# MCU063B_USB.net
KiCad netlist of a schematic drawn in Altium Designer
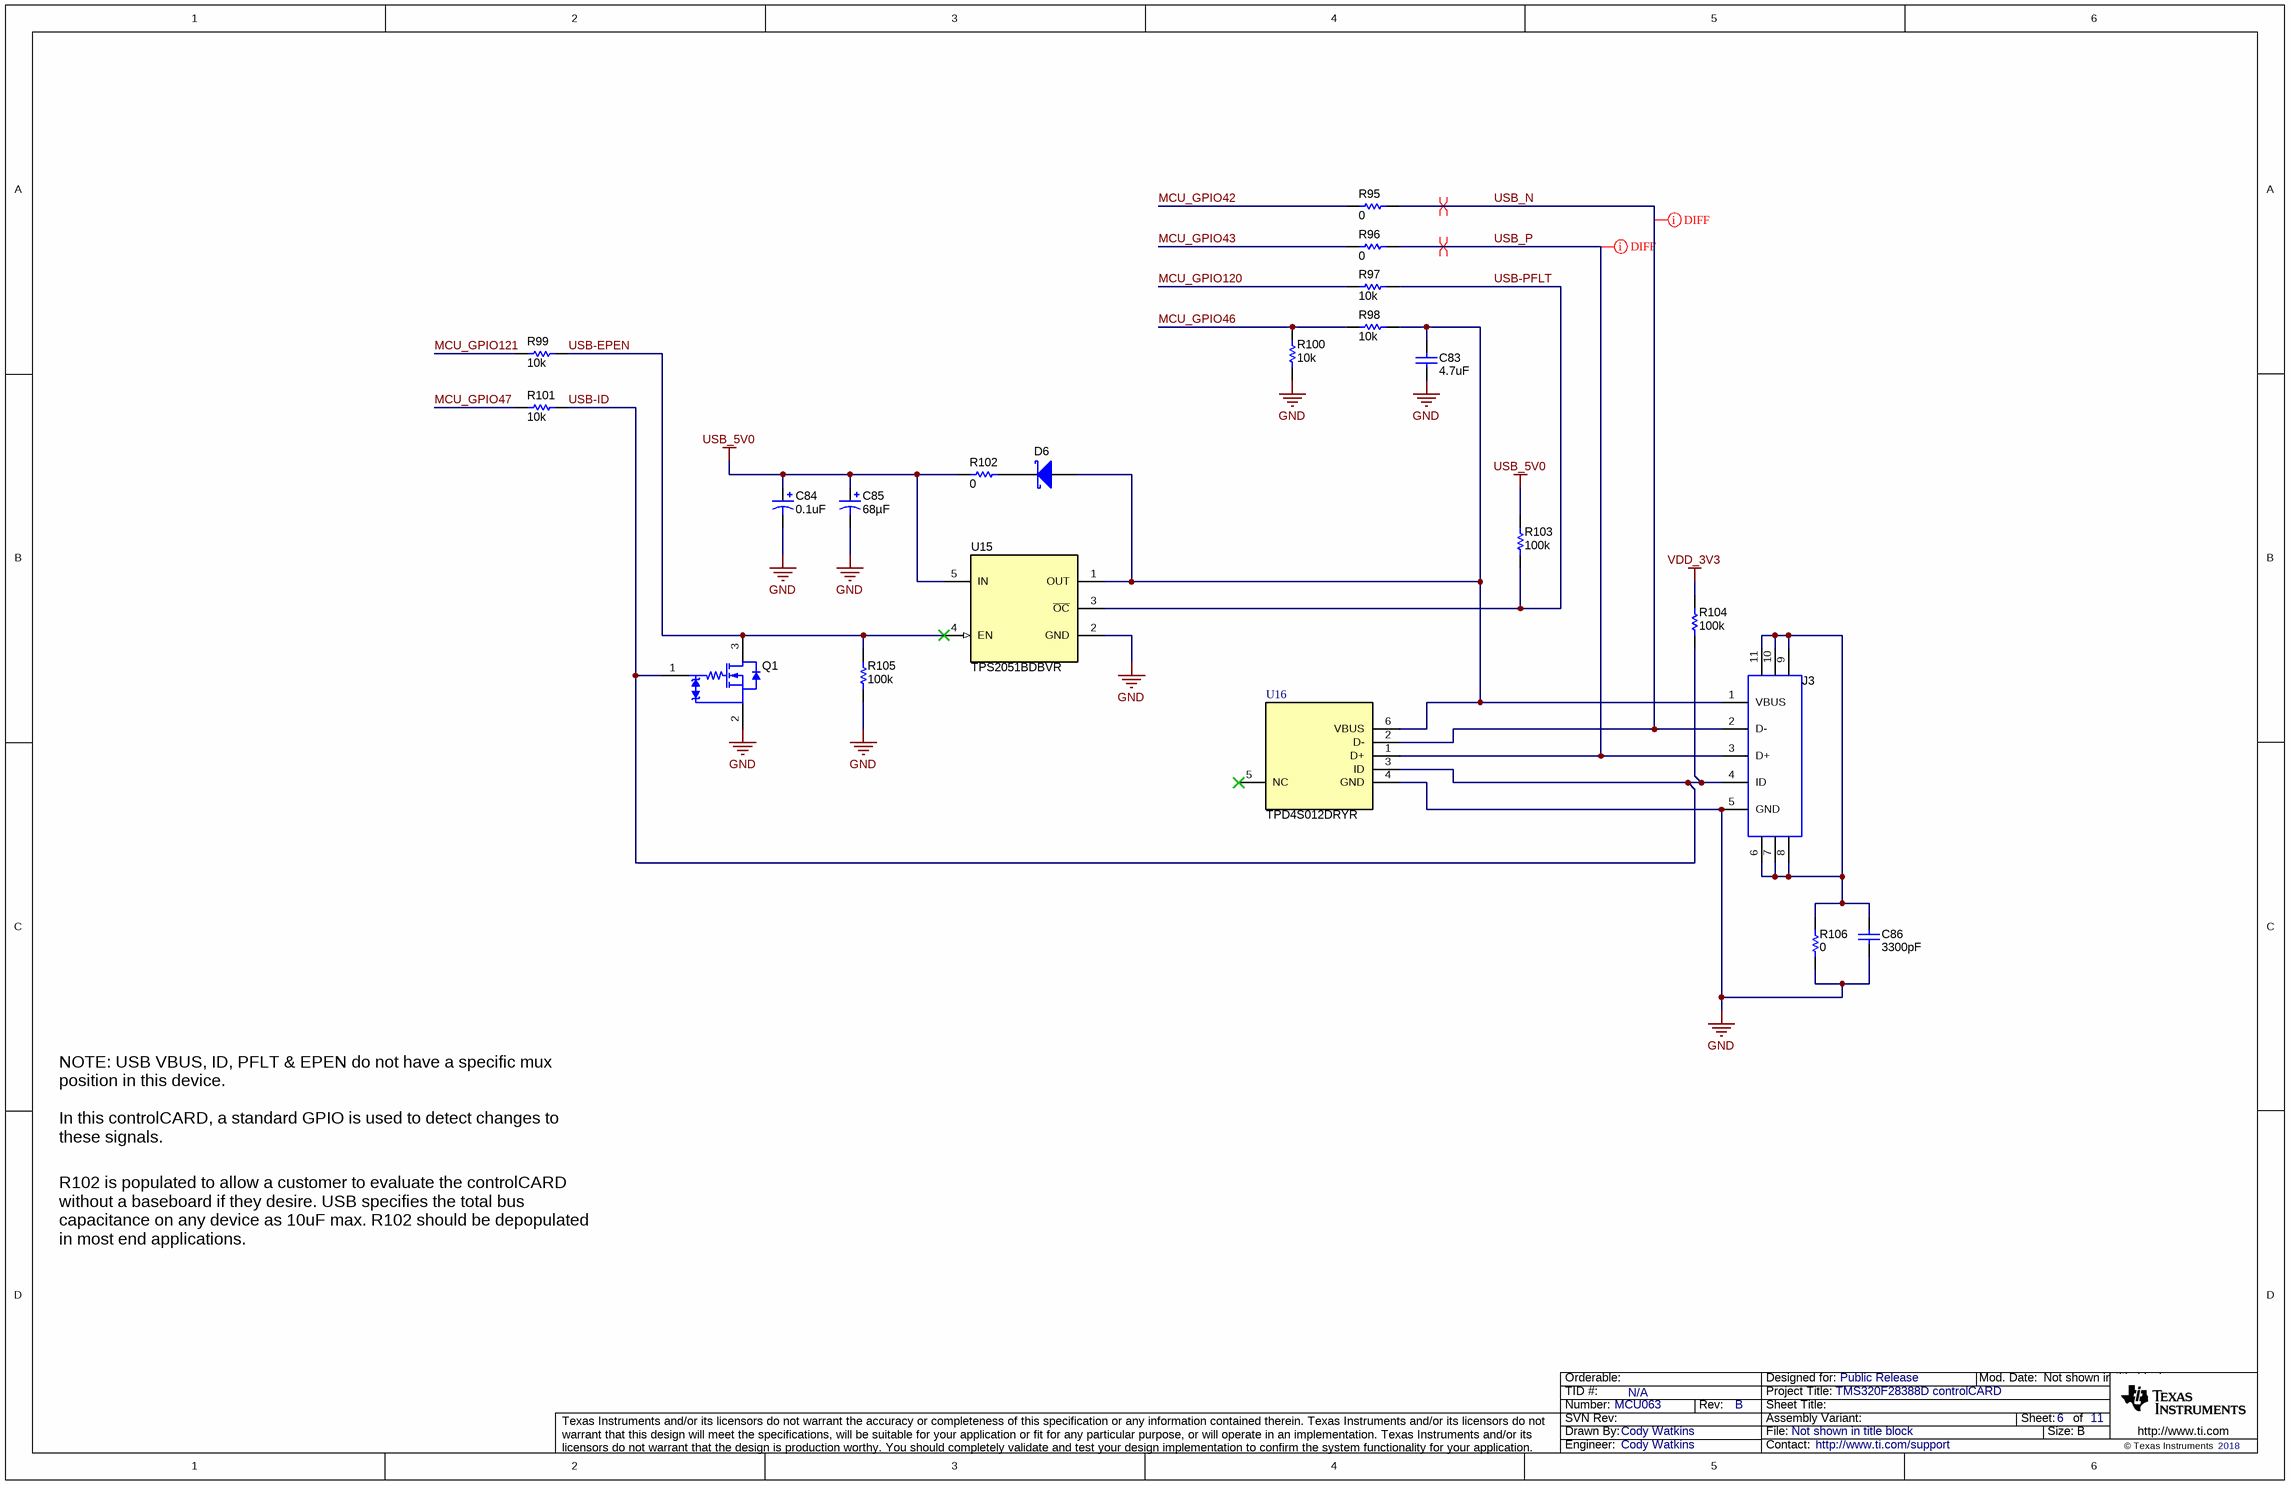
[diagram p0: MCU063B_USB.SchDoc]

(export (version "E")
  (design (tool "Eeschema 10.0.6"))
  (components
    (comp (ref "C83")
      (value "C0603C475K9PACTU")
      (footprint "0603")
      (description "CAP, CERM, 4.7 uF, 6.3 V, +/- 10%, X5R, 0603")
      (fields
        (field (name "MANUFACTURER") "Kemet")
        (field (name "VALUEDISPLAYED") "4.7uF")
        (field (name "PUBLISHER") "Texas Instruments")
      )
      (libsource (lib "Altium Vault - TI") (part "Capacitor"))
    )
    (comp (ref "C84")
      (value "293D104X9035A2TE3")
      (footprint "3216-18")
      (description "CAP, TA, 0.1 uF, 35 V, +/- 10%, 20 ohm, SMD")
      (fields
        (field (name "MANUFACTURER") "Vishay-Sprague")
        (field (name "VALUEDISPLAYED") "0.1uF")
        (field (name "PUBLISHER") "Texas Instruments")
      )
      (libsource (lib "Altium Vault - TI") (part "Cap_Polarized"))
    )
    (comp (ref "C85")
      (value "TLJA686M010R1500")
      (footprint "3216-18")
      (description "CAP, TA, 68 µF, 10 V, +/- 20%, 1.5 ohm, SMD")
      (fields (field (name "MANUFACTURER") "AVX") (field (name "VALUEDISPLAYED") "68µF"))
      (libsource (lib "Altium Vault - TI") (part "Cap_Polarized"))
    )
    (comp (ref "C86")
      (value "CGA2B2X7R1H332K050BA")
      (footprint "0402")
      (description "CAP, CERM, 3300 pF, 50 V, +/- 10%, X7R, AEC-Q200 Grade 1, 0402")
      (fields
        (field (name "MANUFACTURER") "TDK")
        (field (name "VALUEDISPLAYED") "3300pF")
        (field (name "PUBLISHER") "Texas Instruments")
      )
      (libsource (lib "Altium Vault - TI") (part "Capacitor"))
    )
    (comp (ref "D6")
      (value "MBRM110ET1G")
      (footprint "POWERMITE")
      (description "Diode, Schottky, 10 V, 1 A, AEC-Q101, POWERMITE")
      (fields (field (name "MANUFACTURER") "ON Semiconductor"))
      (libsource (lib "Altium Vault - TI") (part "DIODE_SCHOTTKY"))
    )
    (comp (ref "J3")
      (value "1051640001")
      (footprint "Molex_1051640001")
      (description "Receptacle, USB 2.0, Micro B, 5 Position, R/A, SMT")
      (fields (field (name "MANUFACTURER") "Molex") (field (name "PUBLISHER") "Texas Instruments"))
      (libsource (lib "Altium Vault - TI") (part "CONN_USB_MicroMini_6Shld"))
    )
    (comp (ref "Q1")
      (value "NTA7002NT1G")
      (footprint "SOT-416")
      (description "MOSFET, N-CH, 30 V, 0.154 A, AEC-Q101, SOT-416")
      (fields (field (name "MANUFACTURER") "ON Semiconductor"))
      (libsource (lib "Altium Vault - TI") (part "MOSFET_N_D3G1S2_PD5_RES"))
    )
    (comp (ref "R95")
      (value "CRCW04020000Z0ED")
      (footprint "0402")
      (description "RES, 0, 5%, 0.063 W, AEC-Q200 Grade 0, 0402")
      (fields (field (name "VALUEDISPLAYED") "0") (field (name "MANUFACTURER") "Vishay-Dale"))
      (libsource (lib "Altium Vault - TI") (part "Resistor"))
    )
    (comp (ref "R96")
      (value "CRCW04020000Z0ED")
      (footprint "0402")
      (description "RES, 0, 5%, 0.063 W, AEC-Q200 Grade 0, 0402")
      (fields (field (name "VALUEDISPLAYED") "0") (field (name "MANUFACTURER") "Vishay-Dale"))
      (libsource (lib "Altium Vault - TI") (part "Resistor"))
    )
    (comp (ref "R97")
      (value "ERJ-6GEYJ103V")
      (footprint "0805_HV")
      (description "RES, 10 k, 5%, 0.125 W, AEC-Q200 Grade 0, 0805")
      (fields (field (name "MANUFACTURER") "Panasonic") (field (name "VALUEDISPLAYED") "10k"))
      (libsource (lib "Altium Vault - TI") (part "Resistor"))
    )
    (comp (ref "R98")
      (value "ERJ-6GEYJ103V")
      (footprint "0805_HV")
      (description "RES, 10 k, 5%, 0.125 W, AEC-Q200 Grade 0, 0805")
      (fields (field (name "MANUFACTURER") "Panasonic") (field (name "VALUEDISPLAYED") "10k"))
      (libsource (lib "Altium Vault - TI") (part "Resistor"))
    )
    (comp (ref "R99")
      (value "ERJ-6GEYJ103V")
      (footprint "0805_HV")
      (description "RES, 10 k, 5%, 0.125 W, AEC-Q200 Grade 0, 0805")
      (fields (field (name "MANUFACTURER") "Panasonic") (field (name "VALUEDISPLAYED") "10k"))
      (libsource (lib "Altium Vault - TI") (part "Resistor"))
    )
    (comp (ref "R100")
      (value "ERJ-6GEYJ103V")
      (footprint "0805_HV")
      (description "RES, 10 k, 5%, 0.125 W, AEC-Q200 Grade 0, 0805")
      (fields (field (name "MANUFACTURER") "Panasonic") (field (name "VALUEDISPLAYED") "10k"))
      (libsource (lib "Altium Vault - TI") (part "Resistor"))
    )
    (comp (ref "R101")
      (value "ERJ-6GEYJ103V")
      (footprint "0805_HV")
      (description "RES, 10 k, 5%, 0.125 W, AEC-Q200 Grade 0, 0805")
      (fields (field (name "MANUFACTURER") "Panasonic") (field (name "VALUEDISPLAYED") "10k"))
      (libsource (lib "Altium Vault - TI") (part "Resistor"))
    )
    (comp (ref "R102")
      (value "CRCW04020000Z0ED")
      (footprint "0402")
      (description "RES, 0, 5%, 0.063 W, AEC-Q200 Grade 0, 0402")
      (fields (field (name "VALUEDISPLAYED") "0") (field (name "MANUFACTURER") "Vishay-Dale"))
      (libsource (lib "Altium Vault - TI") (part "Resistor"))
    )
    (comp (ref "R103")
      (value "ERJ-3GEYJ104V")
      (footprint "0603")
      (description "RES, 100 k, 5%, 0.1 W, AEC-Q200 Grade 0, 0603")
      (fields
        (field (name "MANUFACTURER") "Panasonic")
        (field (name "VALUEDISPLAYED") "100k")
        (field (name "PUBLISHER") "Texas Instruments")
      )
      (libsource (lib "Altium Vault - TI") (part "Resistor"))
    )
    (comp (ref "R104")
      (value "ERJ-3GEYJ104V")
      (footprint "0603")
      (description "RES, 100 k, 5%, 0.1 W, AEC-Q200 Grade 0, 0603")
      (fields
        (field (name "MANUFACTURER") "Panasonic")
        (field (name "VALUEDISPLAYED") "100k")
        (field (name "PUBLISHER") "Texas Instruments")
      )
      (libsource (lib "Altium Vault - TI") (part "Resistor"))
    )
    (comp (ref "R105")
      (value "ERJ-3GEYJ104V")
      (footprint "0603")
      (description "RES, 100 k, 5%, 0.1 W, AEC-Q200 Grade 0, 0603")
      (fields
        (field (name "MANUFACTURER") "Panasonic")
        (field (name "VALUEDISPLAYED") "100k")
        (field (name "PUBLISHER") "Texas Instruments")
      )
      (libsource (lib "Altium Vault - TI") (part "Resistor"))
    )
    (comp (ref "R106")
      (value "CRCW04020000Z0ED")
      (footprint "0402")
      (description "RES, 0, 5%, 0.063 W, AEC-Q200 Grade 0, 0402")
      (fields (field (name "VALUEDISPLAYED") "0") (field (name "MANUFACTURER") "Vishay-Dale"))
      (libsource (lib "Altium Vault - TI") (part "Resistor"))
    )
    (comp (ref "U15")
      (value "TPS2051BDBVR")
      (footprint "DBV0005A_N")
      (description "Single, Current-Limited, Power-Distribution Switch, DBV0005A (SOT-23-5)")
      (fields
        (field (name "ALTERNATE PARTNUMBER") "TPS2051BDBVT")
        (field (name "MANUFACTURER") "Texas Instruments")
        (field (name "PARTNUMBER") "TPS2051BDBVR")
        (field (name "PUBLISHER") "Texas Instruments")
      )
      (libsource (lib "Altium Vault - TI") (part "TPS2051DBV"))
    )
    (comp (ref "U16")
      (value "TPD4S012DRYR")
      (footprint "DRY0006A")
      (description "4-Channel USB ESD Solution with Power Clamp, DRY0006A (USON-6)")
      (fields (field (name "MANUFACTURER") "Texas Instruments") (field (name "PARTNUMBER") "TPD4S012DRYR"))
      (libsource (lib "Altium Vault - TI") (part "TI-TPD4S012-SON_DRY-6"))
    )
  )
  (nets
    (net (code "1") (name "/MCU_GPIO42") (class "Default")
      (node (ref "R95") (pin "1") (pinfunction "1_1") (pintype "passive"))
    )
    (net (code "2") (name "/MCU_GPIO43") (class "Default")
      (node (ref "R96") (pin "1") (pinfunction "1_1") (pintype "passive"))
    )
    (net (code "3") (name "/MCU_GPIO46") (class "Default")
      (node (ref "R100") (pin "2") (pinfunction "2_2") (pintype "passive"))
      (node (ref "R98") (pin "1") (pinfunction "1_1") (pintype "passive"))
    )
    (net (code "4") (name "/MCU_GPIO47") (class "Default")
      (node (ref "R101") (pin "1") (pinfunction "1_1") (pintype "passive"))
    )
    (net (code "5") (name "/MCU_GPIO120") (class "Default")
      (node (ref "R97") (pin "1") (pinfunction "1_1") (pintype "passive"))
    )
    (net (code "6") (name "/MCU_GPIO121") (class "Default")
      (node (ref "R99") (pin "1") (pinfunction "1_1") (pintype "passive"))
    )
    (net (code "7") (name "/USB-EPEN") (class "Default")
      (node (ref "Q1") (pin "3") (pinfunction "D_3") (pintype "passive"))
      (node (ref "R105") (pin "1") (pinfunction "1_1") (pintype "passive"))
      (node (ref "R99") (pin "2") (pinfunction "2_2") (pintype "passive"))
      (node (ref "U15") (pin "4") (pinfunction "EN_4") (pintype "input"))
    )
    (net (code "8") (name "/USB-ID") (class "Default")
      (node (ref "J3") (pin "4") (pinfunction "ID_4") (pintype "passive"))
      (node (ref "Q1") (pin "1") (pinfunction "G_1") (pintype "passive"))
      (node (ref "R101") (pin "2") (pinfunction "2_2") (pintype "passive"))
      (node (ref "R104") (pin "2") (pinfunction "2_2") (pintype "passive"))
      (node (ref "U16") (pin "3") (pinfunction "ID_3") (pintype "passive"))
    )
    (net (code "9") (name "/USB-PFLT") (class "Default")
      (node (ref "R103") (pin "2") (pinfunction "2_2") (pintype "passive"))
      (node (ref "R97") (pin "2") (pinfunction "2_2") (pintype "passive"))
      (node (ref "U15") (pin "3") (pinfunction "OC_3") (pintype "open_collector"))
    )
    (net (code "10") (name "/USB_N") (class "Default")
      (node (ref "J3") (pin "2") (pinfunction "D-_2") (pintype "passive"))
      (node (ref "R95") (pin "2") (pinfunction "2_2") (pintype "passive"))
      (node (ref "U16") (pin "2") (pinfunction "D-_2") (pintype "passive"))
    )
    (net (code "11") (name "/USB_P") (class "Default")
      (node (ref "J3") (pin "3") (pinfunction "D+_3") (pintype "passive"))
      (node (ref "R96") (pin "2") (pinfunction "2_2") (pintype "passive"))
      (node (ref "U16") (pin "1") (pinfunction "D+_1") (pintype "passive"))
    )
    (net (code "12") (name "GND") (class "Default")
      (node (ref "C83") (pin "2") (pinfunction "2_2") (pintype "passive"))
      (node (ref "C84") (pin "2") (pinfunction "-_2") (pintype "passive"))
      (node (ref "C85") (pin "2") (pinfunction "-_2") (pintype "passive"))
      (node (ref "C86") (pin "1") (pinfunction "1_1") (pintype "passive"))
      (node (ref "J3") (pin "5") (pinfunction "GND_5") (pintype "passive"))
      (node (ref "Q1") (pin "2") (pinfunction "S_2") (pintype "passive"))
      (node (ref "R100") (pin "1") (pinfunction "1_1") (pintype "passive"))
      (node (ref "R105") (pin "2") (pinfunction "2_2") (pintype "passive"))
      (node (ref "R106") (pin "2") (pinfunction "2_2") (pintype "passive"))
      (node (ref "U15") (pin "2") (pinfunction "GND_2") (pintype "power_in"))
      (node (ref "U16") (pin "4") (pinfunction "GND_4") (pintype "power_in"))
    )
    (net (code "13") (name "Net-(C86-Pad2)") (class "Default")
      (node (ref "C86") (pin "2") (pinfunction "2_2") (pintype "passive"))
      (node (ref "J3") (pin "10") (pinfunction "10_10") (pintype "passive"))
      (node (ref "J3") (pin "11") (pinfunction "11_11") (pintype "passive"))
      (node (ref "J3") (pin "6") (pinfunction "6_6") (pintype "passive"))
      (node (ref "J3") (pin "7") (pinfunction "7_7") (pintype "passive"))
      (node (ref "J3") (pin "8") (pinfunction "8_8") (pintype "passive"))
      (node (ref "J3") (pin "9") (pinfunction "9_9") (pintype "passive"))
      (node (ref "R106") (pin "1") (pinfunction "1_1") (pintype "passive"))
    )
    (net (code "14") (name "Net-(D6-A)") (class "Default")
      (node (ref "C83") (pin "1") (pinfunction "1_1") (pintype "passive"))
      (node (ref "D6") (pin "2") (pinfunction "A_2") (pintype "passive"))
      (node (ref "J3") (pin "1") (pinfunction "VBUS_1") (pintype "passive"))
      (node (ref "R98") (pin "2") (pinfunction "2_2") (pintype "passive"))
      (node (ref "U15") (pin "1") (pinfunction "OUT_1") (pintype "power_in"))
      (node (ref "U16") (pin "6") (pinfunction "VBUS_6") (pintype "passive"))
    )
    (net (code "15") (name "Net-(D6-K)") (class "Default")
      (node (ref "D6") (pin "1") (pinfunction "K_1") (pintype "passive"))
      (node (ref "R102") (pin "2") (pinfunction "2_2") (pintype "passive"))
    )
    (net (code "16") (name "USB_5V0") (class "Default")
      (node (ref "C84") (pin "1") (pinfunction "+_1") (pintype "passive"))
      (node (ref "C85") (pin "1") (pinfunction "+_1") (pintype "passive"))
      (node (ref "R102") (pin "1") (pinfunction "1_1") (pintype "passive"))
      (node (ref "R103") (pin "1") (pinfunction "1_1") (pintype "passive"))
      (node (ref "U15") (pin "5") (pinfunction "IN_5") (pintype "power_in"))
    )
    (net (code "17") (name "VDD_3V3") (class "Default")
      (node (ref "R104") (pin "1") (pinfunction "1_1") (pintype "passive"))
    )
    (net (code "18") (name "unconnected-(U16-NC-Pad5)") (class "Default")
      (node (ref "U16") (pin "5") (pinfunction "NC_5") (pintype "passive+no_connect"))
    )
  )
)
